# Half_Slave.net
KiCad netlist of a schematic drawn in Altium Designer
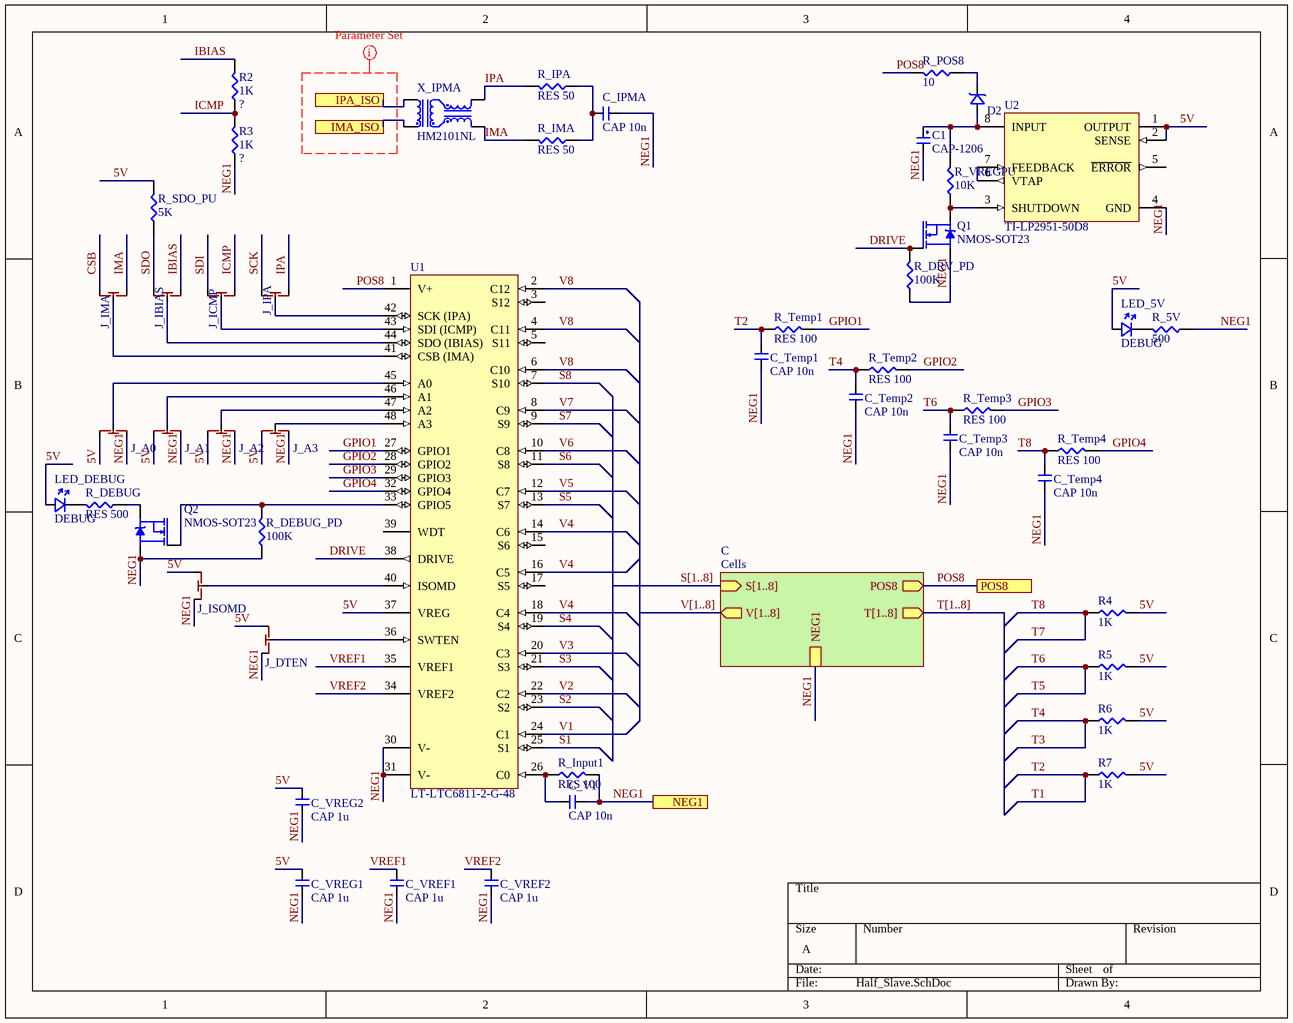
[diagram p0: Half_Slave.SchDoc]

(export (version "E")
  (design (tool "Eeschema 10.0.6"))
  (components
    (comp (ref "C1")
      (value "CAP-1206")
      (footprint "CAPCP3216X16N")
      (libsource (lib "LTC6811") (part "CAP-1206"))
    )
    (comp (ref "C_IPMA")
      (value "CAP 10n")
      (footprint "CAP-0603")
      (description "CAP-0603")
      (libsource (lib "ife18_TS_BMS_LTC6813_v2_Library") (part "CAP-0603"))
    )
    (comp (ref "C_Temp1")
      (value "CAP 10n")
      (footprint "CAP-0603")
      (description "CAP-0603")
      (libsource (lib "altium-import") (part "root_1_CAP-0603_"))
    )
    (comp (ref "C_Temp2")
      (value "CAP 10n")
      (footprint "CAP-0603")
      (description "CAP-0603")
      (libsource (lib "altium-import") (part "root_1_CAP-0603_"))
    )
    (comp (ref "C_Temp3")
      (value "CAP 10n")
      (footprint "CAP-0603")
      (description "CAP-0603")
      (libsource (lib "altium-import") (part "root_1_CAP-0603_"))
    )
    (comp (ref "C_Temp4")
      (value "CAP 10n")
      (footprint "CAP-0603")
      (description "CAP-0603")
      (libsource (lib "altium-import") (part "root_1_CAP-0603_"))
    )
    (comp (ref "C_V1")
      (value "CAP 10n")
      (footprint "CAP-0603")
      (description "CAP-0603")
      (libsource (lib "altium-import") (part "root_2_CAP-0603_"))
    )
    (comp (ref "C_VREF1")
      (value "CAP 1u")
      (footprint "CAP-0603")
      (description "CAP-0603")
      (libsource (lib "altium-import") (part "root_1_CAP-0603_"))
    )
    (comp (ref "C_VREF2")
      (value "CAP 1u")
      (footprint "CAP-0603")
      (description "CAP-0603")
      (libsource (lib "altium-import") (part "root_1_CAP-0603_"))
    )
    (comp (ref "C_VREG1")
      (value "CAP 1u")
      (footprint "CAP-0603")
      (description "CAP-0603")
      (libsource (lib "altium-import") (part "root_1_CAP-0603_"))
    )
    (comp (ref "C_VREG2")
      (value "CAP 1u")
      (footprint "CAP-0603")
      (description "CAP-0603")
      (libsource (lib "altium-import") (part "root_1_CAP-0603_"))
    )
    (comp (ref "D2") (value "?") (footprint "SMB") (libsource (lib "ife19_Elec_Library") (part "DIODE-SMB")))
    (comp (ref "J_A0")
      (value "DPDT Solder Jumper")
      (footprint "DPDT Solder")
      (libsource (lib "LTC6811") (part "DPDT Solder"))
    )
    (comp (ref "J_A1")
      (value "DPDT Solder Jumper")
      (footprint "DPDT Solder")
      (libsource (lib "LTC6811") (part "DPDT Solder"))
    )
    (comp (ref "J_A2")
      (value "DPDT Solder Jumper")
      (footprint "DPDT Solder")
      (libsource (lib "LTC6811") (part "DPDT Solder"))
    )
    (comp (ref "J_A3")
      (value "DPDT Solder Jumper")
      (footprint "DPDT Solder")
      (libsource (lib "LTC6811") (part "DPDT Solder"))
    )
    (comp (ref "J_DTEN")
      (value "DPDT Solder Jumper")
      (footprint "DPDT Solder")
      (libsource (lib "LTC6811") (part "DPDT Solder"))
    )
    (comp (ref "J_IBIAS")
      (value "DPDT Solder Jumper")
      (footprint "DPDT Solder")
      (libsource (lib "LTC6811") (part "DPDT Solder"))
    )
    (comp (ref "J_ICMP")
      (value "DPDT Solder Jumper")
      (footprint "DPDT Solder")
      (libsource (lib "LTC6811") (part "DPDT Solder"))
    )
    (comp (ref "J_IMA")
      (value "DPDT Solder Jumper")
      (footprint "DPDT Solder")
      (libsource (lib "LTC6811") (part "DPDT Solder"))
    )
    (comp (ref "J_IPA")
      (value "DPDT Solder Jumper")
      (footprint "DPDT Solder")
      (libsource (lib "LTC6811") (part "DPDT Solder"))
    )
    (comp (ref "J_ISOMD")
      (value "DPDT Solder Jumper")
      (footprint "DPDT Solder")
      (libsource (lib "LTC6811") (part "DPDT Solder"))
    )
    (comp (ref "LED_5V")
      (value "DEBUG")
      (footprint "LED-0603")
      (description "LED-0603")
      (libsource (lib "altium-import") (part "root_0_LED-0603_"))
    )
    (comp (ref "LED_DEBUG")
      (value "DEBUG")
      (footprint "LED-0603")
      (description "LED-0603")
      (libsource (lib "altium-import") (part "root_0_LED-0603_"))
    )
    (comp (ref "Q1")
      (value "NMOS-SOT23")
      (footprint "SOT23")
      (libsource (lib "ife19_Elec_Library") (part "NMOS-SOT23"))
    )
    (comp (ref "Q2")
      (value "NMOS-SOT23")
      (footprint "SOT23")
      (libsource (lib "ife19_Elec_Library") (part "NMOS-SOT23"))
    )
    (comp (ref "R2")
      (value "1K")
      (footprint "RES-0603")
      (description "RES SMD 0603")
      (fields (field (name "PART") "RES_0603") (field (name "ALTIUM_VALUE") "?"))
      (libsource (lib "IFE") (part "RES"))
    )
    (comp (ref "R3")
      (value "1K")
      (footprint "RES-0603")
      (description "RES SMD 0603")
      (fields (field (name "PART") "RES_0603") (field (name "ALTIUM_VALUE") "?"))
      (libsource (lib "IFE") (part "RES"))
    )
    (comp (ref "R4")
      (value "1K")
      (footprint "RES-0603")
      (libsource (lib "ife19_Elec_Library") (part "RES-0603"))
    )
    (comp (ref "R5")
      (value "1K")
      (footprint "RES-0603")
      (libsource (lib "ife19_Elec_Library") (part "RES-0603"))
    )
    (comp (ref "R6")
      (value "1K")
      (footprint "RES-0603")
      (libsource (lib "ife19_Elec_Library") (part "RES-0603"))
    )
    (comp (ref "R7")
      (value "1K")
      (footprint "RES-0603")
      (libsource (lib "ife19_Elec_Library") (part "RES-0603"))
    )
    (comp (ref "R_5V")
      (value "500")
      (footprint "RES-0603")
      (libsource (lib "altium-import") (part "root_2_RES-0603_"))
    )
    (comp (ref "R_DEBUG")
      (value "RES 500")
      (footprint "RES-0603")
      (libsource (lib "altium-import") (part "root_2_RES-0603_"))
    )
    (comp (ref "R_DEBUG_PD")
      (value "100K")
      (footprint "RES-0603")
      (libsource (lib "ife18_TS_BMS_LTC6813_v2_Library") (part "RES-0603"))
    )
    (comp (ref "R_DRV_PD")
      (value "100K")
      (footprint "RES-0603")
      (libsource (lib "ife18_TS_BMS_LTC6813_v2_Library") (part "RES-0603"))
    )
    (comp (ref "R_IMA")
      (value "RES 50")
      (footprint "RES-0603")
      (libsource (lib "ife18_TS_BMS_LTC6813_v2_Library") (part "RES-0603"))
    )
    (comp (ref "R_Input1")
      (value "RES 100")
      (footprint "RES-0603")
      (libsource (lib "altium-import") (part "root_0_RES-0603_"))
    )
    (comp (ref "R_IPA")
      (value "RES 50")
      (footprint "RES-0603")
      (libsource (lib "ife18_TS_BMS_LTC6813_v2_Library") (part "RES-0603"))
    )
    (comp (ref "R_POS8")
      (value "10")
      (footprint "RES-0603")
      (libsource (lib "ife18_TS_BMS_LTC6813_v2_Library") (part "RES-0603"))
    )
    (comp (ref "R_SDO_PU")
      (value "5K")
      (footprint "RES-0603")
      (libsource (lib "ife18_TS_BMS_LTC6813_v2_Library") (part "RES-0603"))
    )
    (comp (ref "R_Temp1")
      (value "RES 100")
      (footprint "RES-0603")
      (libsource (lib "altium-import") (part "root_0_RES-0603_"))
    )
    (comp (ref "R_Temp2")
      (value "RES 100")
      (footprint "RES-0603")
      (libsource (lib "altium-import") (part "root_0_RES-0603_"))
    )
    (comp (ref "R_Temp3")
      (value "RES 100")
      (footprint "RES-0603")
      (libsource (lib "altium-import") (part "root_0_RES-0603_"))
    )
    (comp (ref "R_Temp4")
      (value "RES 100")
      (footprint "RES-0603")
      (libsource (lib "altium-import") (part "root_0_RES-0603_"))
    )
    (comp (ref "R_VREGPU")
      (value "10K")
      (footprint "RES-0603")
      (libsource (lib "ife18_TS_BMS_LTC6813_v2_Library") (part "RES-0603"))
    )
    (comp (ref "U1")
      (value "LT-LTC6811-2-G-48")
      (footprint "SSOP-48N")
      (libsource (lib "LTC6811") (part "LT-LTC6811-2-G-48"))
    )
    (comp (ref "U2")
      (value "TI-LP2951-50D8")
      (footprint "SOIC127P600X175-8N")
      (libsource (lib "LTC6811") (part "TI-LP2951-50D8"))
    )
    (comp (ref "X_IPMA")
      (value "HM2101NL")
      (footprint "HM2101")
      (libsource (lib "altium-import") (part "root_2_HM2101NL_"))
    )
  )
  (nets
    (net (code "1") (name "/5V") (class "Default")
      (node (ref "C_VREG1") (pin "2") (pinfunction "2_2") (pintype "passive"))
      (node (ref "C_VREG2") (pin "2") (pinfunction "2_2") (pintype "passive"))
      (node (ref "J_A0") (pin "2") (pintype "passive"))
      (node (ref "J_A1") (pin "2") (pintype "passive"))
      (node (ref "J_A2") (pin "2") (pintype "passive"))
      (node (ref "J_A3") (pin "2") (pintype "passive"))
      (node (ref "J_DTEN") (pin "2") (pintype "passive"))
      (node (ref "J_ISOMD") (pin "2") (pintype "passive"))
      (node (ref "LED_5V") (pin "A") (pinfunction "A_A") (pintype "passive"))
      (node (ref "LED_DEBUG") (pin "A") (pinfunction "A_A") (pintype "passive"))
      (node (ref "R4") (pin "2") (pinfunction "2_2") (pintype "passive"))
      (node (ref "R5") (pin "2") (pinfunction "2_2") (pintype "passive"))
      (node (ref "R6") (pin "2") (pinfunction "2_2") (pintype "passive"))
      (node (ref "R7") (pin "2") (pinfunction "2_2") (pintype "passive"))
      (node (ref "R_SDO_PU") (pin "2") (pinfunction "2_2") (pintype "passive"))
      (node (ref "U1") (pin "37") (pinfunction "VREG_37") (pintype "power_in"))
      (node (ref "U2") (pin "1") (pinfunction "OUTPUT_1") (pintype "power_in"))
      (node (ref "U2") (pin "2") (pinfunction "SENSE_2") (pintype "input"))
    )
    (net (code "2") (name "/CSB") (class "Default") (node (ref "J_IMA") (pin "1") (pintype "passive")))
    (net (code "3") (name "/DRIVE") (class "Default")
      (node (ref "Q1") (pin "1") (pinfunction "G_1") (pintype "passive"))
      (node (ref "R_DRV_PD") (pin "2") (pinfunction "2_2") (pintype "passive"))
      (node (ref "U1") (pin "38") (pinfunction "DRIVE_38") (pintype "output"))
    )
    (net (code "4") (name "/GPIO1") (class "Default")
      (node (ref "R_Temp1") (pin "2") (pinfunction "2_2") (pintype "passive"))
      (node (ref "U1") (pin "27") (pinfunction "GPIO1_27") (pintype "bidirectional"))
    )
    (net (code "5") (name "/GPIO2") (class "Default")
      (node (ref "R_Temp2") (pin "2") (pinfunction "2_2") (pintype "passive"))
      (node (ref "U1") (pin "28") (pinfunction "GPIO2_28") (pintype "bidirectional"))
    )
    (net (code "6") (name "/GPIO3") (class "Default")
      (node (ref "R_Temp3") (pin "2") (pinfunction "2_2") (pintype "passive"))
      (node (ref "U1") (pin "29") (pinfunction "GPIO3_29") (pintype "bidirectional"))
    )
    (net (code "7") (name "/GPIO4") (class "Default")
      (node (ref "R_Temp4") (pin "2") (pinfunction "2_2") (pintype "passive"))
      (node (ref "U1") (pin "32") (pinfunction "GPIO4_32") (pintype "bidirectional"))
    )
    (net (code "8") (name "/IBIAS") (class "Default")
      (node (ref "J_IBIAS") (pin "2") (pintype "passive"))
      (node (ref "R2") (pin "2") (pinfunction "2_2") (pintype "passive"))
    )
    (net (code "9") (name "/ICMP") (class "Default")
      (node (ref "J_ICMP") (pin "2") (pintype "passive"))
      (node (ref "R2") (pin "1") (pinfunction "1_1") (pintype "passive"))
      (node (ref "R3") (pin "2") (pinfunction "2_2") (pintype "passive"))
    )
    (net (code "10") (name "/IMA") (class "Default")
      (node (ref "J_IMA") (pin "2") (pintype "passive"))
      (node (ref "R_IMA") (pin "2") (pinfunction "2_2") (pintype "passive"))
      (node (ref "X_IPMA") (pin "4") (pinfunction "4_4") (pintype "passive"))
    )
    (net (code "11") (name "/IMA_ISO") (class "Default")
      (node (ref "X_IPMA") (pin "3") (pinfunction "3_3") (pintype "passive"))
    )
    (net (code "12") (name "/IPA") (class "Default")
      (node (ref "J_IPA") (pin "2") (pintype "passive"))
      (node (ref "R_IPA") (pin "2") (pinfunction "2_2") (pintype "passive"))
      (node (ref "X_IPMA") (pin "6") (pinfunction "6_6") (pintype "passive"))
    )
    (net (code "13") (name "/IPA_ISO") (class "Default")
      (node (ref "X_IPMA") (pin "1") (pinfunction "1_1") (pintype "passive"))
    )
    (net (code "14") (name "/NEG1") (class "Default")
      (node (ref "C1") (pin "2") (pinfunction "2_2") (pintype "passive"))
      (node (ref "C_IPMA") (pin "1") (pinfunction "1_1") (pintype "passive"))
      (node (ref "C_Temp1") (pin "1") (pinfunction "1_1") (pintype "passive"))
      (node (ref "C_Temp2") (pin "1") (pinfunction "1_1") (pintype "passive"))
      (node (ref "C_Temp3") (pin "1") (pinfunction "1_1") (pintype "passive"))
      (node (ref "C_Temp4") (pin "1") (pinfunction "1_1") (pintype "passive"))
      (node (ref "C_V1") (pin "1") (pinfunction "1_1") (pintype "passive"))
      (node (ref "C_VREF1") (pin "1") (pinfunction "1_1") (pintype "passive"))
      (node (ref "C_VREF2") (pin "1") (pinfunction "1_1") (pintype "passive"))
      (node (ref "C_VREG1") (pin "1") (pinfunction "1_1") (pintype "passive"))
      (node (ref "C_VREG2") (pin "1") (pinfunction "1_1") (pintype "passive"))
      (node (ref "J_A0") (pin "1") (pintype "passive"))
      (node (ref "J_A1") (pin "1") (pintype "passive"))
      (node (ref "J_A2") (pin "1") (pintype "passive"))
      (node (ref "J_A3") (pin "1") (pintype "passive"))
      (node (ref "J_DTEN") (pin "1") (pintype "passive"))
      (node (ref "J_ISOMD") (pin "1") (pintype "passive"))
      (node (ref "Q1") (pin "2") (pinfunction "S_2") (pintype "passive"))
      (node (ref "Q2") (pin "2") (pinfunction "S_2") (pintype "passive"))
      (node (ref "R3") (pin "1") (pinfunction "1_1") (pintype "passive"))
      (node (ref "R_5V") (pin "1") (pinfunction "1_1") (pintype "passive"))
      (node (ref "R_DEBUG_PD") (pin "1") (pinfunction "1_1") (pintype "passive"))
      (node (ref "R_DRV_PD") (pin "1") (pinfunction "1_1") (pintype "passive"))
      (node (ref "R_Input1") (pin "2") (pinfunction "2_2") (pintype "passive"))
      (node (ref "U1") (pin "30") (pinfunction "V-_30") (pintype "power_in"))
      (node (ref "U1") (pin "31") (pinfunction "V-_31") (pintype "power_in"))
      (node (ref "U2") (pin "4") (pinfunction "GND_4") (pintype "power_in"))
    )
    (net (code "15") (name "/POS8") (class "Default")
      (node (ref "R_POS8") (pin "2") (pinfunction "2_2") (pintype "passive"))
      (node (ref "U1") (pin "1") (pinfunction "V+_1") (pintype "power_in"))
    )
    (net (code "16") (name "/S1") (class "Default")
      (node (ref "U1") (pin "25") (pinfunction "S1_25") (pintype "bidirectional"))
    )
    (net (code "17") (name "/S2") (class "Default")
      (node (ref "U1") (pin "23") (pinfunction "S2_23") (pintype "bidirectional"))
    )
    (net (code "18") (name "/S3") (class "Default")
      (node (ref "U1") (pin "21") (pinfunction "S3_21") (pintype "bidirectional"))
    )
    (net (code "19") (name "/S4") (class "Default")
      (node (ref "U1") (pin "19") (pinfunction "S4_19") (pintype "bidirectional"))
    )
    (net (code "20") (name "/S5") (class "Default")
      (node (ref "U1") (pin "13") (pinfunction "S7_13") (pintype "bidirectional"))
    )
    (net (code "21") (name "/S6") (class "Default")
      (node (ref "U1") (pin "11") (pinfunction "S8_11") (pintype "bidirectional"))
    )
    (net (code "22") (name "/S7") (class "Default")
      (node (ref "U1") (pin "9") (pinfunction "S9_9") (pintype "bidirectional"))
    )
    (net (code "23") (name "/S8") (class "Default")
      (node (ref "U1") (pin "7") (pinfunction "S10_7") (pintype "bidirectional"))
    )
    (net (code "24") (name "/SCK") (class "Default") (node (ref "J_IPA") (pin "1") (pintype "passive")))
    (net (code "25") (name "/SDI") (class "Default") (node (ref "J_ICMP") (pin "1") (pintype "passive")))
    (net (code "26") (name "/SDO") (class "Default")
      (node (ref "J_IBIAS") (pin "1") (pintype "passive"))
      (node (ref "R_SDO_PU") (pin "1") (pinfunction "1_1") (pintype "passive"))
    )
    (net (code "28") (name "/T2") (class "Default")
      (node (ref "C_Temp1") (pin "2") (pinfunction "2_2") (pintype "passive"))
      (node (ref "R7") (pin "1") (pinfunction "1_1") (pintype "passive"))
      (node (ref "R_Temp1") (pin "1") (pinfunction "1_1") (pintype "passive"))
    )
    (net (code "29") (name "/T4") (class "Default")
      (node (ref "C_Temp2") (pin "2") (pinfunction "2_2") (pintype "passive"))
      (node (ref "R6") (pin "1") (pinfunction "1_1") (pintype "passive"))
      (node (ref "R_Temp2") (pin "1") (pinfunction "1_1") (pintype "passive"))
    )
    (net (code "30") (name "/T6") (class "Default")
      (node (ref "C_Temp3") (pin "2") (pinfunction "2_2") (pintype "passive"))
      (node (ref "R5") (pin "1") (pinfunction "1_1") (pintype "passive"))
      (node (ref "R_Temp3") (pin "1") (pinfunction "1_1") (pintype "passive"))
    )
    (net (code "31") (name "/T8") (class "Default")
      (node (ref "C_Temp4") (pin "2") (pinfunction "2_2") (pintype "passive"))
      (node (ref "R4") (pin "1") (pinfunction "1_1") (pintype "passive"))
      (node (ref "R_Temp4") (pin "1") (pinfunction "1_1") (pintype "passive"))
    )
    (net (code "33") (name "/V1") (class "Default")
      (node (ref "U1") (pin "24") (pinfunction "C1_24") (pintype "input"))
    )
    (net (code "34") (name "/V2") (class "Default")
      (node (ref "U1") (pin "22") (pinfunction "C2_22") (pintype "input"))
    )
    (net (code "35") (name "/V3") (class "Default")
      (node (ref "U1") (pin "20") (pinfunction "C3_20") (pintype "input"))
    )
    (net (code "36") (name "/V4") (class "Default")
      (node (ref "U1") (pin "14") (pinfunction "C6_14") (pintype "input"))
      (node (ref "U1") (pin "16") (pinfunction "C5_16") (pintype "input"))
      (node (ref "U1") (pin "18") (pinfunction "C4_18") (pintype "input"))
    )
    (net (code "37") (name "/V5") (class "Default")
      (node (ref "U1") (pin "12") (pinfunction "C7_12") (pintype "input"))
    )
    (net (code "38") (name "/V6") (class "Default")
      (node (ref "U1") (pin "10") (pinfunction "C8_10") (pintype "input"))
    )
    (net (code "39") (name "/V7") (class "Default")
      (node (ref "U1") (pin "8") (pinfunction "C9_8") (pintype "input"))
    )
    (net (code "40") (name "/V8") (class "Default")
      (node (ref "U1") (pin "2") (pinfunction "C12_2") (pintype "input"))
      (node (ref "U1") (pin "4") (pinfunction "C11_4") (pintype "input"))
      (node (ref "U1") (pin "6") (pinfunction "C10_6") (pintype "input"))
    )
    (net (code "41") (name "/VREF1") (class "Default")
      (node (ref "C_VREF1") (pin "2") (pinfunction "2_2") (pintype "passive"))
      (node (ref "U1") (pin "35") (pinfunction "VREF1_35") (pintype "passive"))
    )
    (net (code "42") (name "/VREF2") (class "Default")
      (node (ref "C_VREF2") (pin "2") (pinfunction "2_2") (pintype "passive"))
      (node (ref "U1") (pin "34") (pinfunction "VREF2_34") (pintype "passive"))
    )
    (net (code "44") (name "Net-(C_IPMA-Pad2)") (class "Default")
      (node (ref "C_IPMA") (pin "2") (pinfunction "2_2") (pintype "passive"))
      (node (ref "R_IMA") (pin "1") (pinfunction "1_1") (pintype "passive"))
      (node (ref "R_IPA") (pin "1") (pinfunction "1_1") (pintype "passive"))
    )
    (net (code "45") (name "Net-(D2-PadK)") (class "Default")
      (node (ref "D2") (pin "K") (pinfunction "K_K") (pintype "passive"))
      (node (ref "R_POS8") (pin "1") (pinfunction "1_1") (pintype "passive"))
    )
    (net (code "46") (name "Net-(LED_5V-PadK)") (class "Default")
      (node (ref "LED_5V") (pin "K") (pinfunction "K_K") (pintype "passive"))
      (node (ref "R_5V") (pin "2") (pinfunction "2_2") (pintype "passive"))
    )
    (net (code "47") (name "Net-(LED_DEBUG-PadK)") (class "Default")
      (node (ref "LED_DEBUG") (pin "K") (pinfunction "K_K") (pintype "passive"))
      (node (ref "R_DEBUG") (pin "2") (pinfunction "2_2") (pintype "passive"))
    )
    (net (code "48") (name "Net-(Q1-D)") (class "Default")
      (node (ref "Q1") (pin "3") (pinfunction "D_3") (pintype "passive"))
      (node (ref "R_VREGPU") (pin "1") (pinfunction "1_1") (pintype "passive"))
      (node (ref "U2") (pin "3") (pinfunction "SHUTDOWN_3") (pintype "input"))
    )
    (net (code "49") (name "Net-(Q2-D)") (class "Default")
      (node (ref "Q2") (pin "3") (pinfunction "D_3") (pintype "passive"))
      (node (ref "R_DEBUG") (pin "1") (pinfunction "1_1") (pintype "passive"))
    )
    (net (code "50") (name "Net-(Q2-G)") (class "Default")
      (node (ref "Q2") (pin "1") (pinfunction "G_1") (pintype "passive"))
      (node (ref "R_DEBUG_PD") (pin "2") (pinfunction "2_2") (pintype "passive"))
      (node (ref "U1") (pin "33") (pinfunction "GPIO5_33") (pintype "bidirectional"))
    )
    (net (code "51") (name "Net-(U1-A0)") (class "Default")
      (node (ref "J_A0") (pin "3") (pintype "passive"))
      (node (ref "U1") (pin "45") (pinfunction "A0_45") (pintype "input"))
    )
    (net (code "52") (name "Net-(U1-A1)") (class "Default")
      (node (ref "J_A1") (pin "3") (pintype "passive"))
      (node (ref "U1") (pin "46") (pinfunction "A1_46") (pintype "input"))
    )
    (net (code "53") (name "Net-(U1-A2)") (class "Default")
      (node (ref "J_A2") (pin "3") (pintype "passive"))
      (node (ref "U1") (pin "47") (pinfunction "A2_47") (pintype "input"))
    )
    (net (code "54") (name "Net-(U1-A3)") (class "Default")
      (node (ref "J_A3") (pin "3") (pintype "passive"))
      (node (ref "U1") (pin "48") (pinfunction "A3_48") (pintype "input"))
    )
    (net (code "55") (name "Net-(U1-C0)") (class "Default")
      (node (ref "C_V1") (pin "2") (pinfunction "2_2") (pintype "passive"))
      (node (ref "R_Input1") (pin "1") (pinfunction "1_1") (pintype "passive"))
      (node (ref "U1") (pin "26") (pinfunction "C0_26") (pintype "input"))
    )
    (net (code "56") (name "Net-(U1-CSB_(IMA))") (class "Default")
      (node (ref "J_IMA") (pin "3") (pintype "passive"))
      (node (ref "U1") (pin "41") (pinfunction "CSB_(IMA)_41") (pintype "bidirectional"))
    )
    (net (code "57") (name "Net-(U1-ISOMD)") (class "Default")
      (node (ref "J_ISOMD") (pin "3") (pintype "passive"))
      (node (ref "U1") (pin "40") (pinfunction "ISOMD_40") (pintype "input"))
    )
    (net (code "58") (name "Net-(U1-SCK_(IPA))") (class "Default")
      (node (ref "J_IPA") (pin "3") (pintype "passive"))
      (node (ref "U1") (pin "42") (pinfunction "SCK_(IPA)_42") (pintype "bidirectional"))
    )
    (net (code "59") (name "Net-(U1-SDI_(ICMP))") (class "Default")
      (node (ref "J_ICMP") (pin "3") (pintype "passive"))
      (node (ref "U1") (pin "43") (pinfunction "SDI_(ICMP)_43") (pintype "input"))
    )
    (net (code "60") (name "Net-(U1-SDO_(IBIAS))") (class "Default")
      (node (ref "J_IBIAS") (pin "3") (pintype "passive"))
      (node (ref "U1") (pin "44") (pinfunction "SDO_(IBIAS)_44") (pintype "bidirectional"))
    )
    (net (code "61") (name "Net-(U1-SWTEN)") (class "Default")
      (node (ref "J_DTEN") (pin "3") (pintype "passive"))
      (node (ref "U1") (pin "36") (pinfunction "SWTEN_36") (pintype "input"))
    )
    (net (code "62") (name "Net-(U2-FEEDBACK)") (class "Default")
      (node (ref "U2") (pin "6") (pinfunction "VTAP_6") (pintype "output"))
      (node (ref "U2") (pin "7") (pinfunction "FEEDBACK_7") (pintype "input"))
    )
    (net (code "63") (name "Net-(U2-INPUT)") (class "Default")
      (node (ref "C1") (pin "1") (pinfunction "1_1") (pintype "passive"))
      (node (ref "D2") (pin "A") (pinfunction "A_A") (pintype "passive"))
      (node (ref "R_VREGPU") (pin "2") (pinfunction "2_2") (pintype "passive"))
      (node (ref "U2") (pin "8") (pinfunction "INPUT_8") (pintype "power_in"))
    )
    (net (code "64") (name "unconnected-(U1-S5-Pad17)") (class "Default")
      (node (ref "U1") (pin "17") (pinfunction "S5_17") (pintype "bidirectional"))
    )
    (net (code "65") (name "unconnected-(U1-S6-Pad15)") (class "Default")
      (node (ref "U1") (pin "15") (pinfunction "S6_15") (pintype "bidirectional"))
    )
    (net (code "66") (name "unconnected-(U1-S11-Pad5)") (class "Default")
      (node (ref "U1") (pin "5") (pinfunction "S11_5") (pintype "bidirectional"))
    )
    (net (code "67") (name "unconnected-(U1-S12-Pad3)") (class "Default")
      (node (ref "U1") (pin "3") (pinfunction "S12_3") (pintype "bidirectional"))
    )
    (net (code "68") (name "unconnected-(U1-WDT-Pad39)") (class "Default")
      (node (ref "U1") (pin "39") (pinfunction "WDT_39") (pintype "tri_state"))
    )
    (net (code "69") (name "unconnected-(U2-~{ERROR}-Pad5)") (class "Default")
      (node (ref "U2") (pin "5") (pinfunction "~{ERROR}_5") (pintype "output"))
    )
  )
)
